# 2016_FDP_PROPULSION.net
KiCad netlist of a schematic drawn in Altium Designer
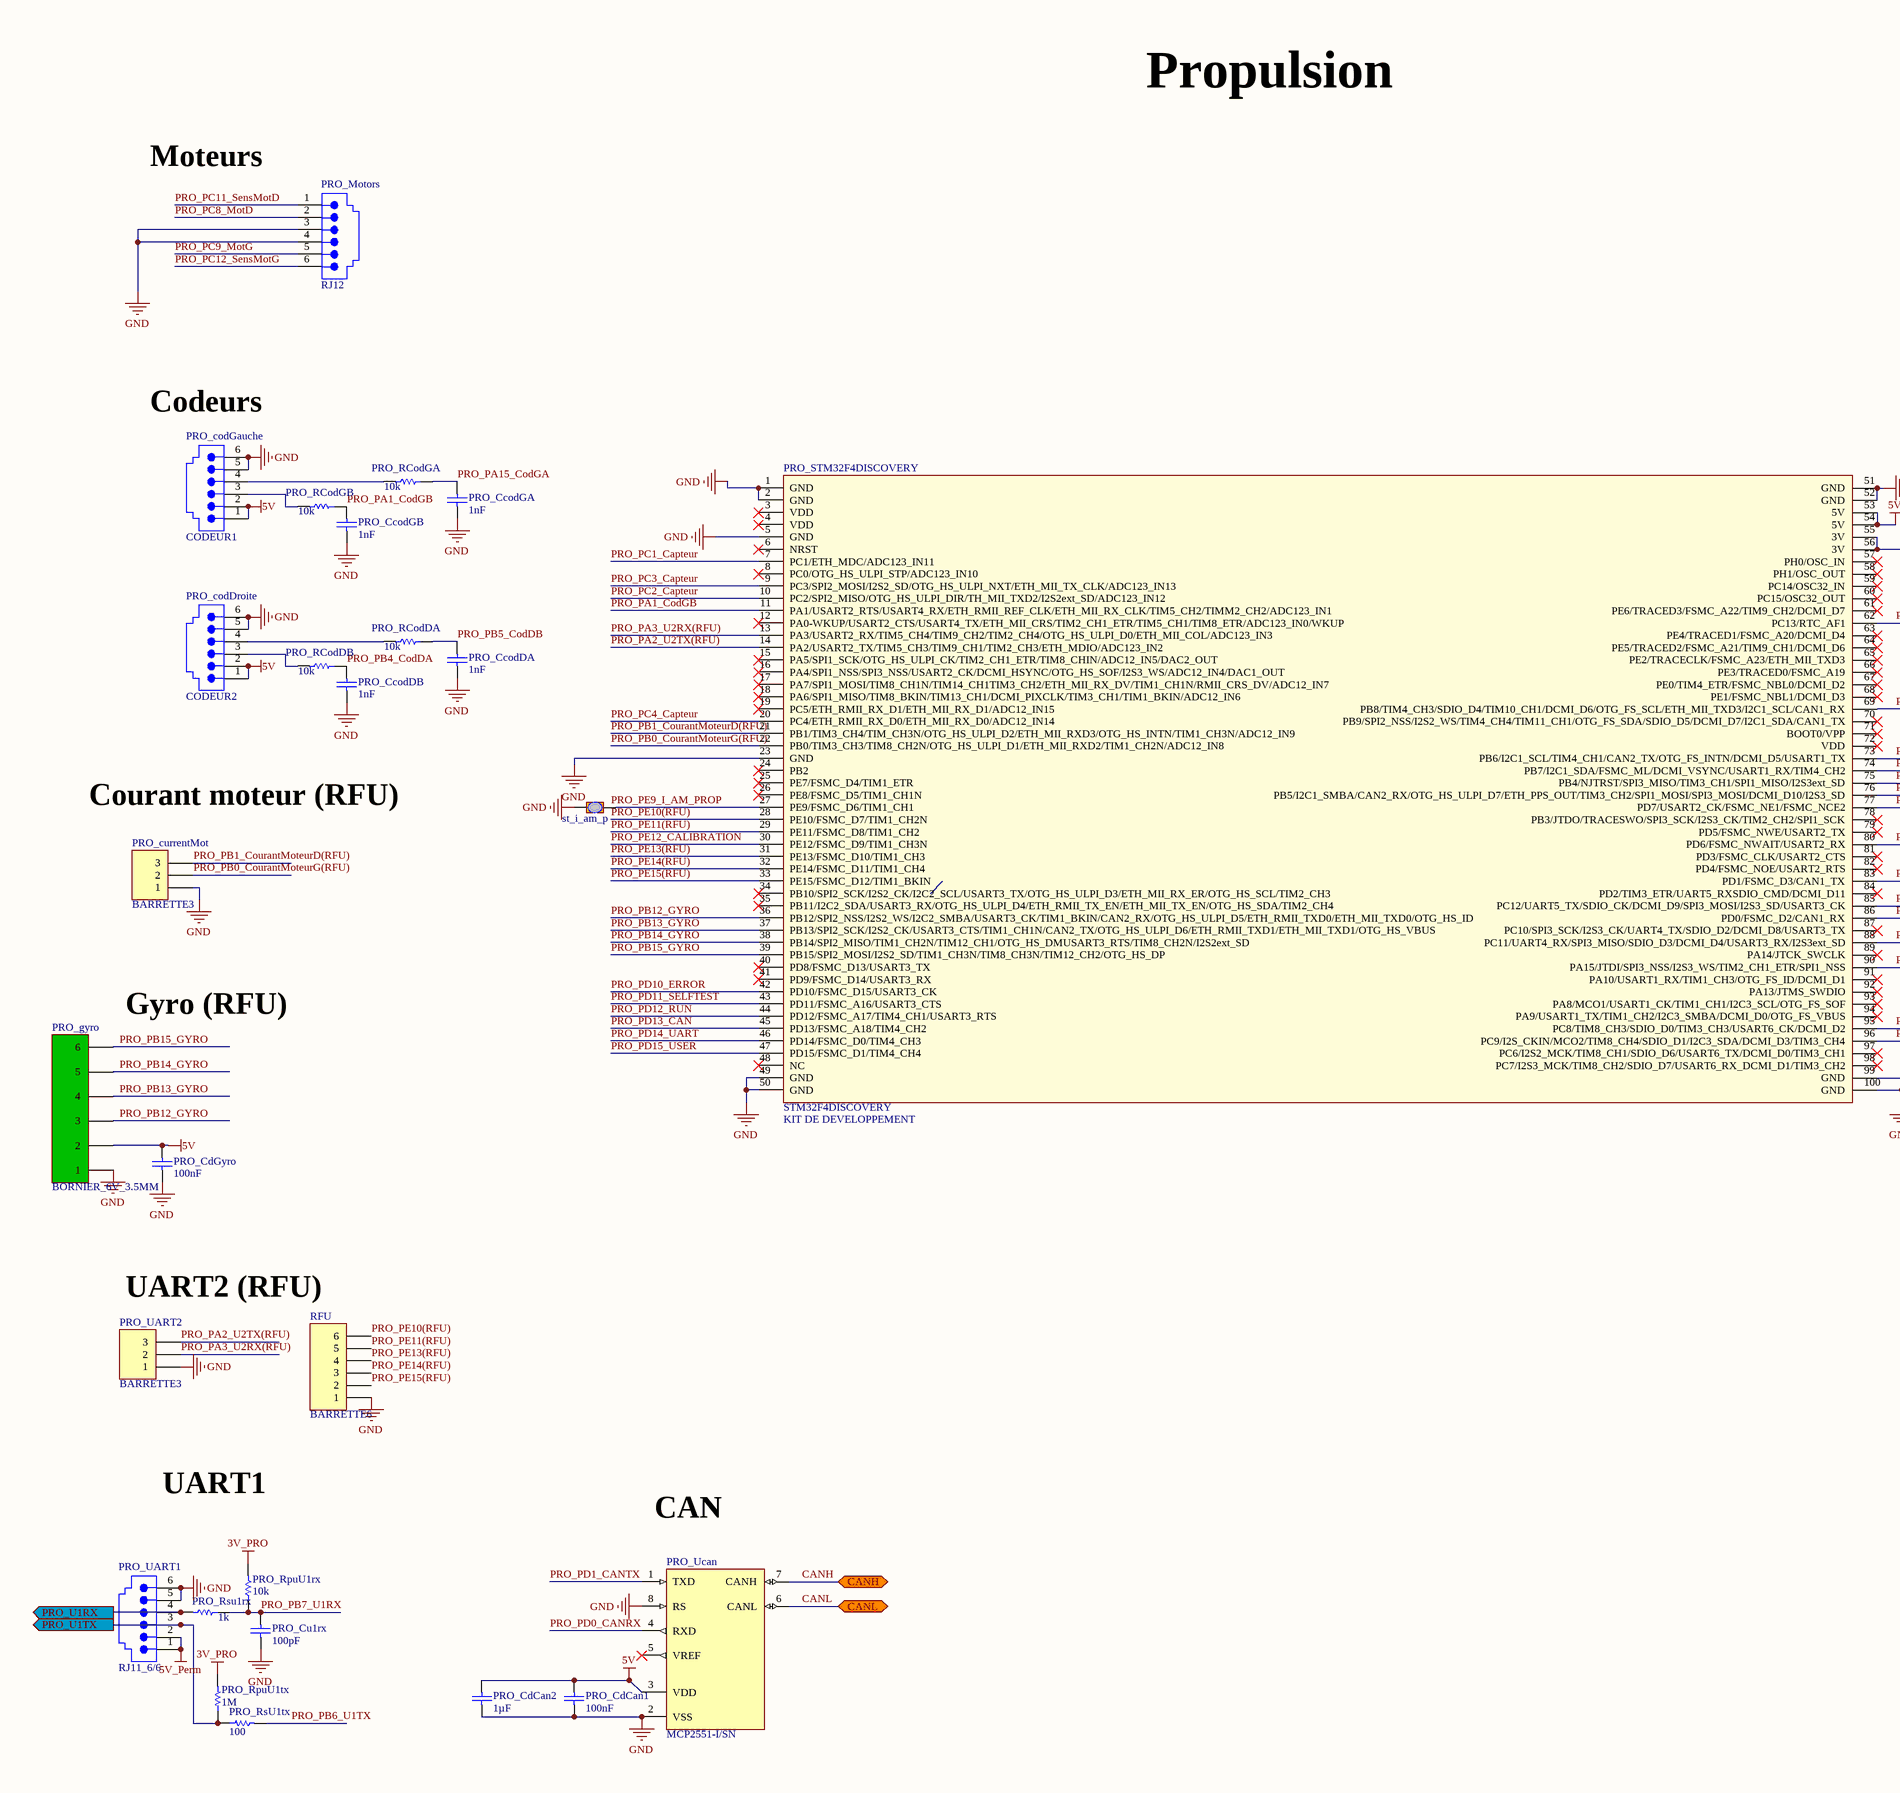
[diagram p0: 2016_FDP_PROPULSION.SchDoc, left]
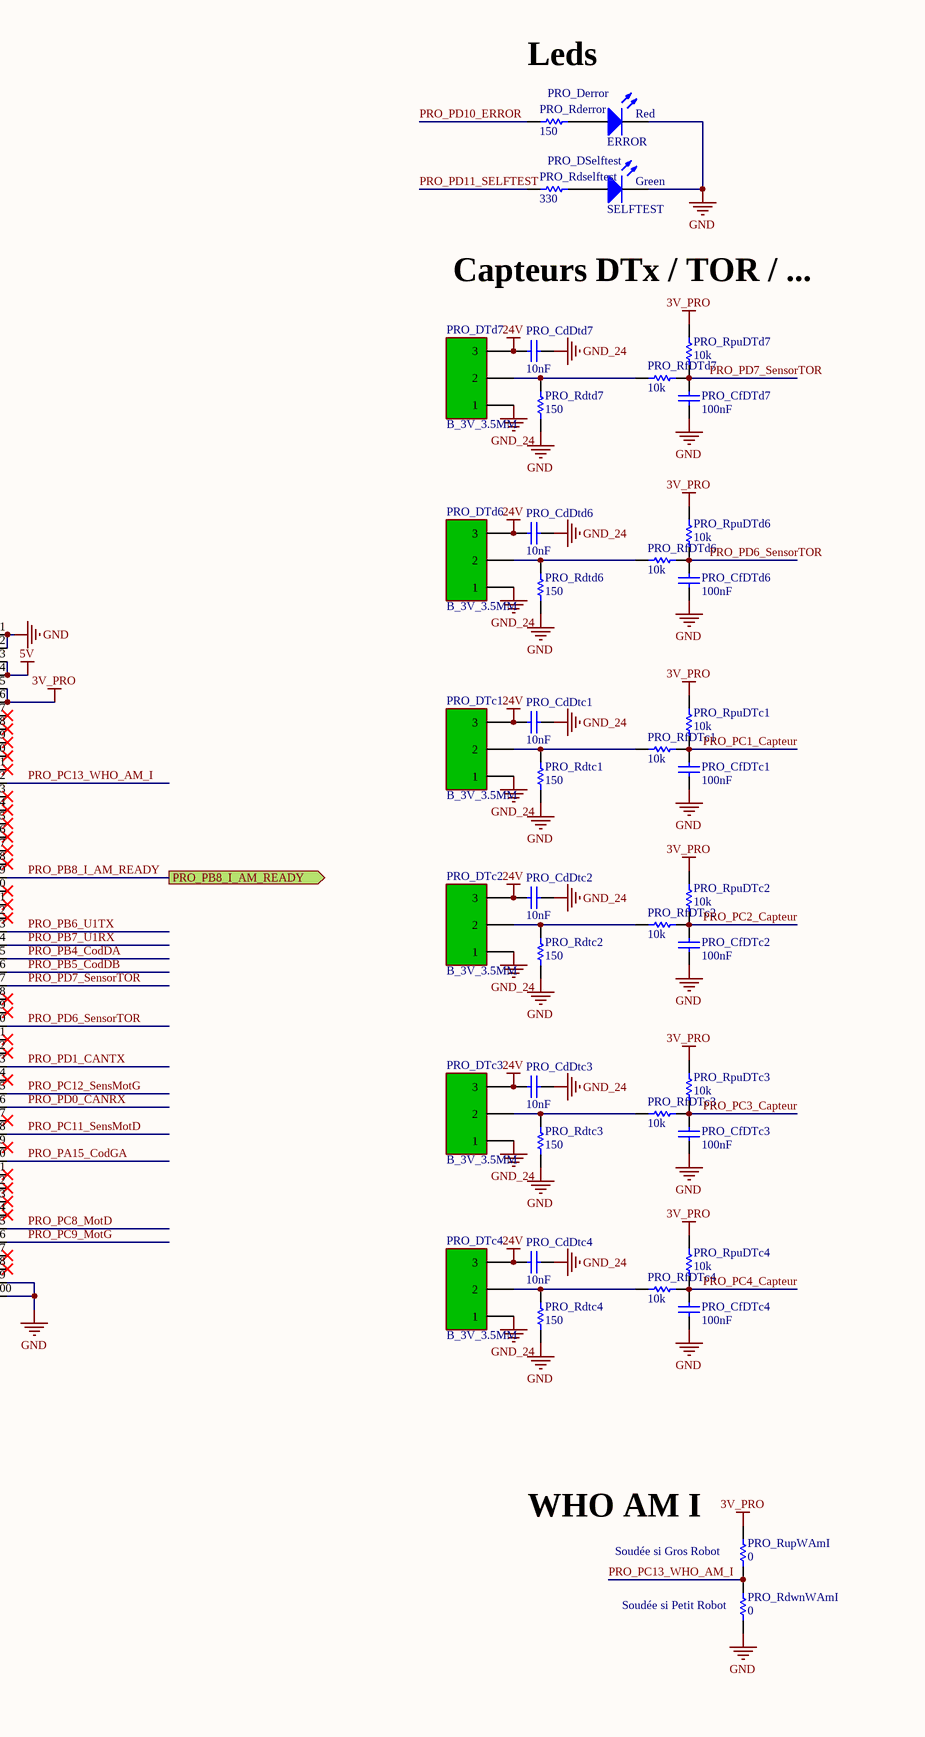
[diagram p1: 2016_FDP_PROPULSION.SchDoc, right]

(export (version "E")
  (design (tool "Eeschema 10.0.6"))
  (components
    (comp (ref "PRO_CcodDA")
      (value "1nF")
      (footprint "C0805_N")
      (description "Capacitor")
      (fields (field (name "PUBLISHER") "Altium Limited"))
      (libsource (lib "_ROBOT") (part "Condensateur"))
    )
    (comp (ref "PRO_CcodDB")
      (value "1nF")
      (footprint "C0805_N")
      (description "Capacitor")
      (fields (field (name "PUBLISHER") "Altium Limited"))
      (libsource (lib "_ROBOT") (part "Condensateur"))
    )
    (comp (ref "PRO_CcodGA")
      (value "1nF")
      (footprint "C0805_N")
      (description "Capacitor")
      (fields (field (name "PUBLISHER") "Altium Limited"))
      (libsource (lib "_ROBOT") (part "Condensateur"))
    )
    (comp (ref "PRO_CcodGB")
      (value "1nF")
      (footprint "C0805_N")
      (description "Capacitor")
      (fields (field (name "PUBLISHER") "Altium Limited"))
      (libsource (lib "_ROBOT") (part "Condensateur"))
    )
    (comp (ref "PRO_CdCan1")
      (value "100nF")
      (footprint "C0805_N")
      (description "Capacitor")
      (fields (field (name "PUBLISHER") "Altium Limited"))
      (libsource (lib "_ROBOT") (part "Condensateur"))
    )
    (comp (ref "PRO_CdCan2")
      (value "1µF")
      (footprint "C0805_N")
      (description "Capacitor")
      (fields (field (name "PUBLISHER") "Altium Limited"))
      (libsource (lib "_ROBOT") (part "Condensateur"))
    )
    (comp (ref "PRO_CdDtc1")
      (value "10nF")
      (footprint "C0805_N")
      (description "Capacitor")
      (fields (field (name "PUBLISHER") "Altium Limited"))
      (libsource (lib "_ROBOT") (part "Condensateur"))
    )
    (comp (ref "PRO_CdDtc2")
      (value "10nF")
      (footprint "C0805_N")
      (description "Capacitor")
      (fields (field (name "PUBLISHER") "Altium Limited"))
      (libsource (lib "_ROBOT") (part "Condensateur"))
    )
    (comp (ref "PRO_CdDtc3")
      (value "10nF")
      (footprint "C0805_N")
      (description "Capacitor")
      (fields (field (name "PUBLISHER") "Altium Limited"))
      (libsource (lib "_ROBOT") (part "Condensateur"))
    )
    (comp (ref "PRO_CdDtc4")
      (value "10nF")
      (footprint "C0805_N")
      (description "Capacitor")
      (fields (field (name "PUBLISHER") "Altium Limited"))
      (libsource (lib "_ROBOT") (part "Condensateur"))
    )
    (comp (ref "PRO_CdDtd6")
      (value "10nF")
      (footprint "C0805_N")
      (description "Capacitor")
      (fields (field (name "PUBLISHER") "Altium Limited"))
      (libsource (lib "_ROBOT") (part "Condensateur"))
    )
    (comp (ref "PRO_CdDtd7")
      (value "10nF")
      (footprint "C0805_N")
      (description "Capacitor")
      (fields (field (name "PUBLISHER") "Altium Limited"))
      (libsource (lib "_ROBOT") (part "Condensateur"))
    )
    (comp (ref "PRO_CdGyro")
      (value "100nF")
      (footprint "C0805_N")
      (description "Capacitor")
      (fields (field (name "PUBLISHER") "Altium Limited"))
      (libsource (lib "_ROBOT") (part "Condensateur"))
    )
    (comp (ref "PRO_CfDTc1")
      (value "100nF")
      (footprint "C0805_N")
      (description "Capacitor")
      (fields (field (name "PUBLISHER") "Altium Limited"))
      (libsource (lib "_ROBOT") (part "Condensateur"))
    )
    (comp (ref "PRO_CfDTc2")
      (value "100nF")
      (footprint "C0805_N")
      (description "Capacitor")
      (fields (field (name "PUBLISHER") "Altium Limited"))
      (libsource (lib "_ROBOT") (part "Condensateur"))
    )
    (comp (ref "PRO_CfDTc3")
      (value "100nF")
      (footprint "C0805_N")
      (description "Capacitor")
      (fields (field (name "PUBLISHER") "Altium Limited"))
      (libsource (lib "_ROBOT") (part "Condensateur"))
    )
    (comp (ref "PRO_CfDTc4")
      (value "100nF")
      (footprint "C0805_N")
      (description "Capacitor")
      (fields (field (name "PUBLISHER") "Altium Limited"))
      (libsource (lib "_ROBOT") (part "Condensateur"))
    )
    (comp (ref "PRO_CfDTd6")
      (value "100nF")
      (footprint "C0805_N")
      (description "Capacitor")
      (fields (field (name "PUBLISHER") "Altium Limited"))
      (libsource (lib "_ROBOT") (part "Condensateur"))
    )
    (comp (ref "PRO_CfDTd7")
      (value "100nF")
      (footprint "C0805_N")
      (description "Capacitor")
      (fields (field (name "PUBLISHER") "Altium Limited"))
      (libsource (lib "_ROBOT") (part "Condensateur"))
    )
    (comp (ref "PRO_codDroite")
      (value "CODEUR2")
      (footprint "RJ11_6/6 - droit")
      (description "Right Angle, Standard Profile, Offset Latch DECconnect, Flangeless PCB Jack")
      (fields (field (name "PUBLISHER") "Altium Limited"))
      (libsource (lib "miniprojet") (part "RJ11_6/6"))
    )
    (comp (ref "PRO_codGauche")
      (value "CODEUR1")
      (footprint "RJ11_6/6 - droit")
      (description "Right Angle, Standard Profile, Offset Latch DECconnect, Flangeless PCB Jack")
      (fields (field (name "PUBLISHER") "Altium Limited"))
      (libsource (lib "miniprojet") (part "RJ11_6/6"))
    )
    (comp (ref "PRO_Cu1rx")
      (value "100pF")
      (footprint "C0805_N")
      (description "Capacitor")
      (fields (field (name "PUBLISHER") "Altium Limited"))
      (libsource (lib "_ROBOT") (part "Condensateur"))
    )
    (comp (ref "PRO_currentMot")
      (value "BARRETTE3")
      (footprint "HE14_3")
      (description "Header, 3-Pin")
      (fields (field (name "PUBLISHER") "Altium Limited"))
      (libsource (lib "Connecteur") (part "BARRETTE3"))
    )
    (comp (ref "PRO_Derror")
      (value "ERROR")
      (footprint "LED_0805")
      (description "Typical LED")
      (fields (field (name "PUBLISHER") "Altium Limited"))
      (libsource (lib "_ROBOT") (part "LED"))
    )
    (comp (ref "PRO_DSelftest")
      (value "SELFTEST")
      (footprint "LED_0805")
      (description "Typical LED")
      (fields (field (name "PUBLISHER") "Altium Limited"))
      (libsource (lib "_ROBOT") (part "LED"))
    )
    (comp (ref "PRO_DTc1")
      (value "B_3V_3.5MM")
      (footprint "BORNIER_3V_3.5MM")
      (libsource (lib "Connecteur") (part "BORNIER_3V_3.5MM"))
    )
    (comp (ref "PRO_DTc2")
      (value "B_3V_3.5MM")
      (footprint "BORNIER_3V_3.5MM")
      (libsource (lib "Connecteur") (part "BORNIER_3V_3.5MM"))
    )
    (comp (ref "PRO_DTc3")
      (value "B_3V_3.5MM")
      (footprint "BORNIER_3V_3.5MM")
      (libsource (lib "Connecteur") (part "BORNIER_3V_3.5MM"))
    )
    (comp (ref "PRO_DTc4")
      (value "B_3V_3.5MM")
      (footprint "BORNIER_3V_3.5MM")
      (libsource (lib "Connecteur") (part "BORNIER_3V_3.5MM"))
    )
    (comp (ref "PRO_DTd6")
      (value "B_3V_3.5MM")
      (footprint "BORNIER_3V_3.5MM")
      (libsource (lib "Connecteur") (part "BORNIER_3V_3.5MM"))
    )
    (comp (ref "PRO_DTd7")
      (value "B_3V_3.5MM")
      (footprint "BORNIER_3V_3.5MM")
      (libsource (lib "Connecteur") (part "BORNIER_3V_3.5MM"))
    )
    (comp (ref "PRO_gyro")
      (value "BORNIER_6V_3.5MM")
      (footprint "BORNIER_6V_3.5MM")
      (libsource (lib "Connecteur") (part "BORNIER_6V_3.5MM"))
    )
    (comp (ref "PRO_Motors")
      (value "RJ12")
      (footprint "RJ11_6/6 - droit")
      (description "Right Angle, Standard Profile, Offset Latch DECconnect, Flangeless PCB Jack")
      (fields (field (name "PUBLISHER") "Altium Limited"))
      (libsource (lib "Connecteur") (part "RJ11_6/6"))
    )
    (comp (ref "PRO_RCodDA")
      (value "10k")
      (footprint "R1206_N")
      (description "Resistor")
      (fields (field (name "PUBLISHER") "Altium Limited"))
      (libsource (lib "_ROBOT") (part "Resistor"))
    )
    (comp (ref "PRO_RCodDB")
      (value "10k")
      (footprint "R1206_N")
      (description "Resistor")
      (fields (field (name "PUBLISHER") "Altium Limited"))
      (libsource (lib "_ROBOT") (part "Resistor"))
    )
    (comp (ref "PRO_RCodGA")
      (value "10k")
      (footprint "R1206_N")
      (description "Resistor")
      (fields (field (name "PUBLISHER") "Altium Limited"))
      (libsource (lib "_ROBOT") (part "Resistor"))
    )
    (comp (ref "PRO_RCodGB")
      (value "10k")
      (footprint "R1206_N")
      (description "Resistor")
      (fields (field (name "PUBLISHER") "Altium Limited"))
      (libsource (lib "_ROBOT") (part "Resistor"))
    )
    (comp (ref "PRO_Rderror")
      (value "150")
      (footprint "R1206_N")
      (description "Resistor")
      (fields (field (name "PUBLISHER") "Altium Limited"))
      (libsource (lib "_ROBOT") (part "Resistor"))
    )
    (comp (ref "PRO_Rdselftest")
      (value "330")
      (footprint "R1206_N")
      (description "Resistor")
      (fields (field (name "PUBLISHER") "Altium Limited"))
      (libsource (lib "_ROBOT") (part "Resistor"))
    )
    (comp (ref "PRO_Rdtc1")
      (value "150")
      (footprint "R1206_N")
      (description "Resistor")
      (fields (field (name "PUBLISHER") "Altium Limited"))
      (libsource (lib "_ROBOT") (part "Resistor"))
    )
    (comp (ref "PRO_Rdtc2")
      (value "150")
      (footprint "R1206_N")
      (description "Resistor")
      (fields (field (name "PUBLISHER") "Altium Limited"))
      (libsource (lib "_ROBOT") (part "Resistor"))
    )
    (comp (ref "PRO_Rdtc3")
      (value "150")
      (footprint "R1206_N")
      (description "Resistor")
      (fields (field (name "PUBLISHER") "Altium Limited"))
      (libsource (lib "_ROBOT") (part "Resistor"))
    )
    (comp (ref "PRO_Rdtc4")
      (value "150")
      (footprint "R1206_N")
      (description "Resistor")
      (fields (field (name "PUBLISHER") "Altium Limited"))
      (libsource (lib "_ROBOT") (part "Resistor"))
    )
    (comp (ref "PRO_Rdtd6")
      (value "150")
      (footprint "R1206_N")
      (description "Resistor")
      (fields (field (name "PUBLISHER") "Altium Limited"))
      (libsource (lib "_ROBOT") (part "Resistor"))
    )
    (comp (ref "PRO_Rdtd7")
      (value "150")
      (footprint "R1206_N")
      (description "Resistor")
      (fields (field (name "PUBLISHER") "Altium Limited"))
      (libsource (lib "_ROBOT") (part "Resistor"))
    )
    (comp (ref "PRO_RdwnWAmI")
      (value "0")
      (footprint "R1206_N")
      (description "Resistor")
      (fields (field (name "PUBLISHER") "Altium Limited"))
      (libsource (lib "_ROBOT") (part "Resistor"))
    )
    (comp (ref "PRO_RfDTc1")
      (value "10k")
      (footprint "R1206_N")
      (description "Resistor")
      (fields (field (name "PUBLISHER") "Altium Limited"))
      (libsource (lib "_ROBOT") (part "Resistor"))
    )
    (comp (ref "PRO_RfDTc2")
      (value "10k")
      (footprint "R1206_N")
      (description "Resistor")
      (fields (field (name "PUBLISHER") "Altium Limited"))
      (libsource (lib "_ROBOT") (part "Resistor"))
    )
    (comp (ref "PRO_RfDTc3")
      (value "10k")
      (footprint "R1206_N")
      (description "Resistor")
      (fields (field (name "PUBLISHER") "Altium Limited"))
      (libsource (lib "_ROBOT") (part "Resistor"))
    )
    (comp (ref "PRO_RfDTc4")
      (value "10k")
      (footprint "R1206_N")
      (description "Resistor")
      (fields (field (name "PUBLISHER") "Altium Limited"))
      (libsource (lib "_ROBOT") (part "Resistor"))
    )
    (comp (ref "PRO_RfDTd6")
      (value "10k")
      (footprint "R1206_N")
      (description "Resistor")
      (fields (field (name "PUBLISHER") "Altium Limited"))
      (libsource (lib "_ROBOT") (part "Resistor"))
    )
    (comp (ref "PRO_RfDTd7")
      (value "10k")
      (footprint "R1206_N")
      (description "Resistor")
      (fields (field (name "PUBLISHER") "Altium Limited"))
      (libsource (lib "_ROBOT") (part "Resistor"))
    )
    (comp (ref "PRO_RpuDTc1")
      (value "10k")
      (footprint "R1206_N")
      (description "Resistor")
      (fields (field (name "PUBLISHER") "Altium Limited"))
      (libsource (lib "_ROBOT") (part "Resistor"))
    )
    (comp (ref "PRO_RpuDTc2")
      (value "10k")
      (footprint "R1206_N")
      (description "Resistor")
      (fields (field (name "PUBLISHER") "Altium Limited"))
      (libsource (lib "_ROBOT") (part "Resistor"))
    )
    (comp (ref "PRO_RpuDTc3")
      (value "10k")
      (footprint "R1206_N")
      (description "Resistor")
      (fields (field (name "PUBLISHER") "Altium Limited"))
      (libsource (lib "_ROBOT") (part "Resistor"))
    )
    (comp (ref "PRO_RpuDTc4")
      (value "10k")
      (footprint "R1206_N")
      (description "Resistor")
      (fields (field (name "PUBLISHER") "Altium Limited"))
      (libsource (lib "_ROBOT") (part "Resistor"))
    )
    (comp (ref "PRO_RpuDTd6")
      (value "10k")
      (footprint "R1206_N")
      (description "Resistor")
      (fields (field (name "PUBLISHER") "Altium Limited"))
      (libsource (lib "_ROBOT") (part "Resistor"))
    )
    (comp (ref "PRO_RpuDTd7")
      (value "10k")
      (footprint "R1206_N")
      (description "Resistor")
      (fields (field (name "PUBLISHER") "Altium Limited"))
      (libsource (lib "_ROBOT") (part "Resistor"))
    )
    (comp (ref "PRO_RpuU1rx")
      (value "10k")
      (footprint "R1206_N")
      (description "Resistor")
      (fields (field (name "PUBLISHER") "Altium Limited"))
      (libsource (lib "_ROBOT") (part "Resistor"))
    )
    (comp (ref "PRO_RpuU1tx")
      (value "1M")
      (footprint "R1206_N")
      (description "Resistor")
      (fields (field (name "PUBLISHER") "Altium Limited"))
      (libsource (lib "_ROBOT") (part "Resistor"))
    )
    (comp (ref "PRO_Rsu1rx")
      (value "1k")
      (footprint "R1206_N")
      (description "Resistor")
      (fields (field (name "PUBLISHER") "Altium Limited"))
      (libsource (lib "_ROBOT") (part "Resistor"))
    )
    (comp (ref "PRO_RsU1tx")
      (value "100")
      (footprint "R1206_N")
      (description "Resistor")
      (fields (field (name "PUBLISHER") "Altium Limited"))
      (libsource (lib "_ROBOT") (part "Resistor"))
    )
    (comp (ref "PRO_RupWAmI")
      (value "0")
      (footprint "R1206_N")
      (description "Resistor")
      (fields (field (name "PUBLISHER") "Altium Limited"))
      (libsource (lib "_ROBOT") (part "Resistor"))
    )
    (comp (ref "PRO_STM32F4DISCOVERY")
      (value "STM32F4DISCOVERY")
      (footprint "STM32_F4DISCOVERY")
      (description "KIT DE DEVELOPPEMENT POUR MICROCONTROLEUR STM32F407VGT6")
      (fields (field (name "TYPE") "KIT DE DEVELOPPEMENT"))
      (libsource (lib "circuits integres") (part "STM32F4DISCOVERY"))
    )
    (comp (ref "PRO_UART1")
      (value "RJ11_6/6")
      (footprint "RJ11_6/6 - droit")
      (description "Right Angle, Standard Profile, Offset Latch DECconnect, Flangeless PCB Jack")
      (fields (field (name "PUBLISHER") "Altium Limited"))
      (libsource (lib "Connecteur") (part "RJ11_6/6"))
    )
    (comp (ref "PRO_UART2")
      (value "BARRETTE3")
      (footprint "HE14_3")
      (description "Header, 3-Pin")
      (fields (field (name "PUBLISHER") "Altium Limited"))
      (libsource (lib "Connecteur") (part "BARRETTE3"))
    )
    (comp (ref "PRO_Ucan")
      (value "MCP2551-I/SN")
      (footprint "SO8_N")
      (description "High-Speed CAN Transceiver, 8-Pin SOIC, Industrial Temperature")
      (fields (field (name "PUBLISHER") "Damien Guitton"))
      (libsource (lib "Circuit intégré") (part "MCP2551-I/SN"))
    )
    (comp (ref "RFU")
      (value "BARRETTE6")
      (footprint "HE14_6")
      (description "Header, 6-Pin")
      (fields (field (name "PUBLISHER") "Altium Limited"))
      (libsource (lib "Connecteur") (part "BARRETTE6"))
    )
    (comp (ref "st_i_am_p")
      (value "Goutte Strap_2")
      (footprint "Goutte Strap_2 Pads_Clearance 0.254mm")
      (fields (field (name "PUBLISHER") "Damien Guitton"))
      (libsource (lib "DG_Connecteur") (part "Goutte Strap_2"))
    )
  )
  (nets
    (net (code "1") (name "/CANH") (class "Default")
      (node (ref "PRO_Ucan") (pin "7") (pinfunction "CANH_7") (pintype "bidirectional"))
    )
    (net (code "2") (name "/CANL") (class "Default")
      (node (ref "PRO_Ucan") (pin "6") (pinfunction "CANL_6") (pintype "bidirectional"))
    )
    (net (code "3") (name "/PRO_PA1_CodGB") (class "Default")
      (node (ref "PRO_CcodGB") (pin "2") (pinfunction "2_2") (pintype "passive"))
      (node (ref "PRO_RCodGB") (pin "1") (pinfunction "1_1") (pintype "passive"))
      (node (ref "PRO_STM32F4DISCOVERY") (pin "11") (pinfunction "PA1/USART2_RTS/USART4_RX/ETH_RMII_REF_CLK/ETH_MII_RX_CLK/TIM5_CH2/TIMM2_CH2/ADC123_IN1_11") (pintype "passive"))
    )
    (net (code "4") (name "/PRO_PA2_U2TX(RFU)") (class "Default")
      (node (ref "PRO_STM32F4DISCOVERY") (pin "14") (pinfunction "PA2/USART2_TX/TIM5_CH3/TIM9_CH1/TIM2_CH3/ETH_MDIO/ADC123_IN2_14") (pintype "passive"))
      (node (ref "PRO_UART2") (pin "3") (pinfunction "3_3") (pintype "passive"))
    )
    (net (code "5") (name "/PRO_PA3_U2RX(RFU)") (class "Default")
      (node (ref "PRO_STM32F4DISCOVERY") (pin "13") (pinfunction "PA3/USART2_RX/TIM5_CH4/TIM9_CH2/TIM2_CH4/OTG_HS_ULPI_D0/ETH_MII_COL/ADC123_IN3_13") (pintype "passive"))
      (node (ref "PRO_UART2") (pin "2") (pinfunction "2_2") (pintype "passive"))
    )
    (net (code "6") (name "/PRO_PA15_CodGA") (class "Default")
      (node (ref "PRO_CcodGA") (pin "2") (pinfunction "2_2") (pintype "passive"))
      (node (ref "PRO_RCodGA") (pin "1") (pinfunction "1_1") (pintype "passive"))
      (node (ref "PRO_STM32F4DISCOVERY") (pin "90") (pinfunction "PA15/JTDI/SPI3_NSS/I2S3_WS/TIM2_CH1_ETR/SPI1_NSS_90") (pintype "passive"))
    )
    (net (code "7") (name "/PRO_PB0_CourantMoteurG(RFU)") (class "Default")
      (node (ref "PRO_STM32F4DISCOVERY") (pin "22") (pinfunction "PB0/TIM3_CH3/TIM8_CH2N/OTG_HS_ULPI_D1/ETH_MII_RXD2/TIM1_CH2N/ADC12_IN8_22") (pintype "passive"))
      (node (ref "PRO_currentMot") (pin "2") (pinfunction "2_2") (pintype "passive"))
    )
    (net (code "8") (name "/PRO_PB1_CourantMoteurD(RFU)") (class "Default")
      (node (ref "PRO_STM32F4DISCOVERY") (pin "21") (pinfunction "PB1/TIM3_CH4/TIM_CH3N/OTG_HS_ULPI_D2/ETH_MII_RXD3/OTG_HS_INTN/TIM1_CH3N/ADC12_IN9_21") (pintype "passive"))
      (node (ref "PRO_currentMot") (pin "3") (pinfunction "3_3") (pintype "passive"))
    )
    (net (code "9") (name "/PRO_PB4_CodDA") (class "Default")
      (node (ref "PRO_CcodDB") (pin "2") (pinfunction "2_2") (pintype "passive"))
      (node (ref "PRO_RCodDB") (pin "1") (pinfunction "1_1") (pintype "passive"))
      (node (ref "PRO_STM32F4DISCOVERY") (pin "75") (pinfunction "PB4/NJTRST/SPI3_MISO/TIM3_CH1/SPI1_MISO/I2S3ext_SD_75") (pintype "passive"))
    )
    (net (code "10") (name "/PRO_PB5_CodDB") (class "Default")
      (node (ref "PRO_CcodDA") (pin "2") (pinfunction "2_2") (pintype "passive"))
      (node (ref "PRO_RCodDA") (pin "1") (pinfunction "1_1") (pintype "passive"))
      (node (ref "PRO_STM32F4DISCOVERY") (pin "76") (pinfunction "PB5/I2C1_SMBA/CAN2_RX/OTG_HS_ULPI_D7/ETH_PPS_OUT/TIM3_CH2/SPI1_MOSI/SPI3_MOSI/DCMI_D10/I2S3_SD_76") (pintype "passive"))
    )
    (net (code "11") (name "/PRO_PB6_U1TX") (class "Default")
      (node (ref "PRO_RsU1tx") (pin "2") (pinfunction "2_2") (pintype "passive"))
      (node (ref "PRO_STM32F4DISCOVERY") (pin "73") (pinfunction "PB6/I2C1_SCL/TIM4_CH1/CAN2_TX/OTG_FS_INTN/DCMI_D5/USART1_TX_73") (pintype "passive"))
    )
    (net (code "12") (name "/PRO_PB7_U1RX") (class "Default")
      (node (ref "PRO_Cu1rx") (pin "2") (pinfunction "2_2") (pintype "passive"))
      (node (ref "PRO_RpuU1rx") (pin "1") (pinfunction "1_1") (pintype "passive"))
      (node (ref "PRO_Rsu1rx") (pin "1") (pinfunction "1_1") (pintype "passive"))
      (node (ref "PRO_STM32F4DISCOVERY") (pin "74") (pinfunction "PB7/I2C1_SDA/FSMC_ML/DCMI_VSYNC/USART1_RX/TIM4_CH2_74") (pintype "passive"))
    )
    (net (code "13") (name "/PRO_PB8_I_AM_READY") (class "Default")
      (node (ref "PRO_STM32F4DISCOVERY") (pin "69") (pinfunction "PB8/TIM4_CH3/SDIO_D4/TIM10_CH1/DCMI_D6/OTG_FS_SCL/ETH_MII_TXD3/I2C1_SCL/CAN1_RX_69") (pintype "passive"))
    )
    (net (code "14") (name "/PRO_PB12_GYRO") (class "Default")
      (node (ref "PRO_STM32F4DISCOVERY") (pin "36") (pinfunction "PB12/SPI2_NSS/I2S2_WS/I2C2_SMBA/USART3_CK/TIM1_BKIN/CAN2_RX/OTG_HS_ULPI_D5/ETH_RMII_TXD0/ETH_MII_TXD0/OTG_HS_ID_36") (pintype "passive"))
      (node (ref "PRO_gyro") (pin "3") (pinfunction "3_3") (pintype "passive"))
    )
    (net (code "15") (name "/PRO_PB13_GYRO") (class "Default")
      (node (ref "PRO_STM32F4DISCOVERY") (pin "37") (pinfunction "PB13/SPI2_SCK/I2S2_CK/USART3_CTS/TIM1_CH1N/CAN2_TX/OTG_HS_ULPI_D6/ETH_RMII_TXD1/ETH_MII_TXD1/OTG_HS_VBUS_37") (pintype "passive"))
      (node (ref "PRO_gyro") (pin "4") (pinfunction "4_4") (pintype "passive"))
    )
    (net (code "16") (name "/PRO_PB14_GYRO") (class "Default")
      (node (ref "PRO_STM32F4DISCOVERY") (pin "38") (pinfunction "PB14/SPI2_MISO/TIM1_CH2N/TIM12_CH1/OTG_HS_DMUSART3_RTS/TIM8_CH2N/I2S2ext_SD_38") (pintype "passive"))
      (node (ref "PRO_gyro") (pin "5") (pinfunction "5_5") (pintype "passive"))
    )
    (net (code "17") (name "/PRO_PB15_GYRO") (class "Default")
      (node (ref "PRO_STM32F4DISCOVERY") (pin "39") (pinfunction "PB15/SPI2_MOSI/I2S2_SD/TIM1_CH3N/TIM8_CH3N/TIM12_CH2/OTG_HS_DP_39") (pintype "passive"))
      (node (ref "PRO_gyro") (pin "6") (pinfunction "6_6") (pintype "passive"))
    )
    (net (code "18") (name "/PRO_PC1_Capteur") (class "Default")
      (node (ref "PRO_CfDTc1") (pin "2") (pinfunction "2_2") (pintype "passive"))
      (node (ref "PRO_RfDTc1") (pin "2") (pinfunction "2_2") (pintype "passive"))
      (node (ref "PRO_RpuDTc1") (pin "1") (pinfunction "1_1") (pintype "passive"))
      (node (ref "PRO_STM32F4DISCOVERY") (pin "7") (pinfunction "PC1/ETH_MDC/ADC123_IN11_7") (pintype "passive"))
    )
    (net (code "19") (name "/PRO_PC2_Capteur") (class "Default")
      (node (ref "PRO_CfDTc2") (pin "2") (pinfunction "2_2") (pintype "passive"))
      (node (ref "PRO_RfDTc2") (pin "2") (pinfunction "2_2") (pintype "passive"))
      (node (ref "PRO_RpuDTc2") (pin "1") (pinfunction "1_1") (pintype "passive"))
      (node (ref "PRO_STM32F4DISCOVERY") (pin "10") (pinfunction "PC2/SPI2_MISO/OTG_HS_ULPI_DIR/TH_MII_TXD2/I2S2ext_SD/ADC123_IN12_10") (pintype "passive"))
    )
    (net (code "20") (name "/PRO_PC3_Capteur") (class "Default")
      (node (ref "PRO_CfDTc3") (pin "2") (pinfunction "2_2") (pintype "passive"))
      (node (ref "PRO_RfDTc3") (pin "2") (pinfunction "2_2") (pintype "passive"))
      (node (ref "PRO_RpuDTc3") (pin "1") (pinfunction "1_1") (pintype "passive"))
      (node (ref "PRO_STM32F4DISCOVERY") (pin "9") (pinfunction "PC3/SPI2_MOSI/I2S2_SD/OTG_HS_ULPI_NXT/ETH_MII_TX_CLK/ADC123_IN13_9") (pintype "passive"))
    )
    (net (code "21") (name "/PRO_PC4_Capteur") (class "Default")
      (node (ref "PRO_CfDTc4") (pin "2") (pinfunction "2_2") (pintype "passive"))
      (node (ref "PRO_RfDTc4") (pin "2") (pinfunction "2_2") (pintype "passive"))
      (node (ref "PRO_RpuDTc4") (pin "1") (pinfunction "1_1") (pintype "passive"))
      (node (ref "PRO_STM32F4DISCOVERY") (pin "20") (pinfunction "PC4/ETH_RMII_RX_D0/ETH_MII_RX_D0/ADC12_IN14_20") (pintype "passive"))
    )
    (net (code "22") (name "/PRO_PC8_MotD") (class "Default")
      (node (ref "PRO_Motors") (pin "2") (pinfunction "2_2") (pintype "passive"))
      (node (ref "PRO_STM32F4DISCOVERY") (pin "95") (pinfunction "PC8/TIM8_CH3/SDIO_D0/TIM3_CH3/USART6_CK/DCMI_D2_95") (pintype "passive"))
    )
    (net (code "23") (name "/PRO_PC9_MotG") (class "Default")
      (node (ref "PRO_Motors") (pin "5") (pinfunction "5_5") (pintype "passive"))
      (node (ref "PRO_STM32F4DISCOVERY") (pin "96") (pinfunction "PC9/I2S_CKIN/MCO2/TIM8_CH4/SDIO_D1/I2C3_SDA/DCMI_D3/TIM3_CH4_96") (pintype "passive"))
    )
    (net (code "24") (name "/PRO_PC11_SensMotD") (class "Default")
      (node (ref "PRO_Motors") (pin "1") (pinfunction "1_1") (pintype "passive"))
      (node (ref "PRO_STM32F4DISCOVERY") (pin "88") (pinfunction "PC11/UART4_RX/SPI3_MISO/SDIO_D3/DCMI_D4/USART3_RX/I2S3ext_SD_88") (pintype "passive"))
    )
    (net (code "25") (name "/PRO_PC12_SensMotG") (class "Default")
      (node (ref "PRO_Motors") (pin "6") (pinfunction "6_6") (pintype "passive"))
      (node (ref "PRO_STM32F4DISCOVERY") (pin "85") (pinfunction "PC12/UART5_TX/SDIO_CK/DCMI_D9/SPI3_MOSI/I2S3_SD/USART3_CK_85") (pintype "passive"))
    )
    (net (code "26") (name "/PRO_PC13_WHO_AM_I") (class "Default")
      (node (ref "PRO_RdwnWAmI") (pin "2") (pinfunction "2_2") (pintype "passive"))
      (node (ref "PRO_RupWAmI") (pin "1") (pinfunction "1_1") (pintype "passive"))
      (node (ref "PRO_STM32F4DISCOVERY") (pin "62") (pinfunction "PC13/RTC_AF1_62") (pintype "passive"))
    )
    (net (code "27") (name "/PRO_PD0_CANRX") (class "Default")
      (node (ref "PRO_STM32F4DISCOVERY") (pin "86") (pinfunction "PD0/FSMC_D2/CAN1_RX_86") (pintype "passive"))
      (node (ref "PRO_Ucan") (pin "4") (pinfunction "RXD_4") (pintype "output"))
    )
    (net (code "28") (name "/PRO_PD1_CANTX") (class "Default")
      (node (ref "PRO_STM32F4DISCOVERY") (pin "83") (pinfunction "PD1/FSMC_D3/CAN1_TX_83") (pintype "passive"))
      (node (ref "PRO_Ucan") (pin "1") (pinfunction "TXD_1") (pintype "input"))
    )
    (net (code "29") (name "/PRO_PD6_SensorTOR") (class "Default")
      (node (ref "PRO_CfDTd6") (pin "2") (pinfunction "2_2") (pintype "passive"))
      (node (ref "PRO_RfDTd6") (pin "2") (pinfunction "2_2") (pintype "passive"))
      (node (ref "PRO_RpuDTd6") (pin "1") (pinfunction "1_1") (pintype "passive"))
      (node (ref "PRO_STM32F4DISCOVERY") (pin "80") (pinfunction "PD6/FSMC_NWAIT/USART2_RX_80") (pintype "passive"))
    )
    (net (code "30") (name "/PRO_PD7_SensorTOR") (class "Default")
      (node (ref "PRO_CfDTd7") (pin "2") (pinfunction "2_2") (pintype "passive"))
      (node (ref "PRO_RfDTd7") (pin "2") (pinfunction "2_2") (pintype "passive"))
      (node (ref "PRO_RpuDTd7") (pin "1") (pinfunction "1_1") (pintype "passive"))
      (node (ref "PRO_STM32F4DISCOVERY") (pin "77") (pinfunction "PD7/USART2_CK/FSMC_NE1/FSMC_NCE2_77") (pintype "passive"))
    )
    (net (code "31") (name "/PRO_PD10_ERROR") (class "Default")
      (node (ref "PRO_Rderror") (pin "1") (pinfunction "1_1") (pintype "passive"))
      (node (ref "PRO_STM32F4DISCOVERY") (pin "42") (pinfunction "PD10/FSMC_D15/USART3_CK_42") (pintype "passive"))
    )
    (net (code "32") (name "/PRO_PD11_SELFTEST") (class "Default")
      (node (ref "PRO_Rdselftest") (pin "1") (pinfunction "1_1") (pintype "passive"))
      (node (ref "PRO_STM32F4DISCOVERY") (pin "43") (pinfunction "PD11/FSMC_A16/USART3_CTS_43") (pintype "passive"))
    )
    (net (code "33") (name "/PRO_PD12_RUN") (class "Default")
      (node (ref "PRO_STM32F4DISCOVERY") (pin "44") (pinfunction "PD12/FSMC_A17/TIM4_CH1/USART3_RTS_44") (pintype "passive"))
    )
    (net (code "34") (name "/PRO_PD13_CAN") (class "Default")
      (node (ref "PRO_STM32F4DISCOVERY") (pin "45") (pinfunction "PD13/FSMC_A18/TIM4_CH2_45") (pintype "passive"))
    )
    (net (code "35") (name "/PRO_PD14_UART") (class "Default")
      (node (ref "PRO_STM32F4DISCOVERY") (pin "46") (pinfunction "PD14/FSMC_D0/TIM4_CH3_46") (pintype "passive"))
    )
    (net (code "36") (name "/PRO_PD15_USER") (class "Default")
      (node (ref "PRO_STM32F4DISCOVERY") (pin "47") (pinfunction "PD15/FSMC_D1/TIM4_CH4_47") (pintype "passive"))
    )
    (net (code "38") (name "/PRO_PE10(RFU)") (class "Default")
      (node (ref "PRO_STM32F4DISCOVERY") (pin "28") (pinfunction "PE10/FSMC_D7/TIM1_CH2N_28") (pintype "passive"))
      (node (ref "RFU") (pin "6") (pinfunction "6_6") (pintype "passive"))
    )
    (net (code "39") (name "/PRO_PE11(RFU)") (class "Default")
      (node (ref "PRO_STM32F4DISCOVERY") (pin "29") (pinfunction "PE11/FSMC_D8/TIM1_CH2_29") (pintype "passive"))
      (node (ref "RFU") (pin "5") (pinfunction "5_5") (pintype "passive"))
    )
    (net (code "40") (name "/PRO_PE12_CALIBRATION") (class "Default")
      (node (ref "PRO_STM32F4DISCOVERY") (pin "30") (pinfunction "PE12/FSMC_D9/TIM1_CH3N_30") (pintype "passive"))
    )
    (net (code "41") (name "/PRO_PE13(RFU)") (class "Default")
      (node (ref "PRO_STM32F4DISCOVERY") (pin "31") (pinfunction "PE13/FSMC_D10/TIM1_CH3_31") (pintype "passive"))
      (node (ref "RFU") (pin "4") (pinfunction "4_4") (pintype "passive"))
    )
    (net (code "42") (name "/PRO_PE14(RFU)") (class "Default")
      (node (ref "PRO_STM32F4DISCOVERY") (pin "32") (pinfunction "PE14/FSMC_D11/TIM1_CH4_32") (pintype "passive"))
      (node (ref "RFU") (pin "3") (pinfunction "3_3") (pintype "passive"))
    )
    (net (code "43") (name "/PRO_PE15(RFU)") (class "Default")
      (node (ref "PRO_STM32F4DISCOVERY") (pin "33") (pinfunction "PE15/FSMC_D12/TIM1_BKIN_33") (pintype "passive"))
      (node (ref "RFU") (pin "2") (pinfunction "2_2") (pintype "passive"))
    )
    (net (code "44") (name "/PRO_U1RX") (class "Default")
      (node (ref "PRO_Rsu1rx") (pin "2") (pinfunction "2_2") (pintype "passive"))
      (node (ref "PRO_UART1") (pin "4") (pinfunction "4_4") (pintype "passive"))
    )
    (net (code "45") (name "/PRO_U1TX") (class "Default")
      (node (ref "PRO_RpuU1tx") (pin "1") (pinfunction "1_1") (pintype "passive"))
      (node (ref "PRO_RsU1tx") (pin "1") (pinfunction "1_1") (pintype "passive"))
      (node (ref "PRO_UART1") (pin "3") (pinfunction "3_3") (pintype "passive"))
    )
    (net (code "46") (name "3V_PRO") (class "Default")
      (node (ref "PRO_RpuDTc1") (pin "2") (pinfunction "2_2") (pintype "passive"))
      (node (ref "PRO_RpuDTc2") (pin "2") (pinfunction "2_2") (pintype "passive"))
      (node (ref "PRO_RpuDTc3") (pin "2") (pinfunction "2_2") (pintype "passive"))
      (node (ref "PRO_RpuDTc4") (pin "2") (pinfunction "2_2") (pintype "passive"))
      (node (ref "PRO_RpuDTd6") (pin "2") (pinfunction "2_2") (pintype "passive"))
      (node (ref "PRO_RpuDTd7") (pin "2") (pinfunction "2_2") (pintype "passive"))
      (node (ref "PRO_RpuU1rx") (pin "2") (pinfunction "2_2") (pintype "passive"))
      (node (ref "PRO_RpuU1tx") (pin "2") (pinfunction "2_2") (pintype "passive"))
      (node (ref "PRO_RupWAmI") (pin "2") (pinfunction "2_2") (pintype "passive"))
      (node (ref "PRO_STM32F4DISCOVERY") (pin "55") (pinfunction "3V_55") (pintype "passive"))
      (node (ref "PRO_STM32F4DISCOVERY") (pin "56") (pinfunction "3V_56") (pintype "passive"))
    )
    (net (code "47") (name "5V") (class "Default")
      (node (ref "PRO_CdCan1") (pin "2") (pinfunction "2_2") (pintype "passive"))
      (node (ref "PRO_CdCan2") (pin "2") (pinfunction "2_2") (pintype "passive"))
      (node (ref "PRO_CdGyro") (pin "2") (pinfunction "2_2") (pintype "passive"))
      (node (ref "PRO_STM32F4DISCOVERY") (pin "53") (pinfunction "5V_53") (pintype "passive"))
      (node (ref "PRO_STM32F4DISCOVERY") (pin "54") (pinfunction "5V_54") (pintype "passive"))
      (node (ref "PRO_Ucan") (pin "3") (pinfunction "VDD_3") (pintype "power_in"))
      (node (ref "PRO_codDroite") (pin "1") (pinfunction "1_1") (pintype "passive"))
      (node (ref "PRO_codDroite") (pin "2") (pinfunction "2_2") (pintype "passive"))
      (node (ref "PRO_codGauche") (pin "1") (pinfunction "1_1") (pintype "passive"))
      (node (ref "PRO_codGauche") (pin "2") (pinfunction "2_2") (pintype "passive"))
      (node (ref "PRO_gyro") (pin "2") (pinfunction "2_2") (pintype "passive"))
    )
    (net (code "48") (name "5V_Perm") (class "Default")
      (node (ref "PRO_UART1") (pin "1") (pinfunction "1_1") (pintype "passive"))
      (node (ref "PRO_UART1") (pin "2") (pinfunction "2_2") (pintype "passive"))
    )
    (net (code "49") (name "24V") (class "Default")
      (node (ref "PRO_CdDtc1") (pin "2") (pinfunction "2_2") (pintype "passive"))
      (node (ref "PRO_CdDtc2") (pin "2") (pinfunction "2_2") (pintype "passive"))
      (node (ref "PRO_CdDtc3") (pin "2") (pinfunction "2_2") (pintype "passive"))
      (node (ref "PRO_CdDtc4") (pin "2") (pinfunction "2_2") (pintype "passive"))
      (node (ref "PRO_CdDtd6") (pin "2") (pinfunction "2_2") (pintype "passive"))
      (node (ref "PRO_CdDtd7") (pin "2") (pinfunction "2_2") (pintype "passive"))
      (node (ref "PRO_DTc1") (pin "3") (pinfunction "3_3") (pintype "passive"))
      (node (ref "PRO_DTc2") (pin "3") (pinfunction "3_3") (pintype "passive"))
      (node (ref "PRO_DTc3") (pin "3") (pinfunction "3_3") (pintype "passive"))
      (node (ref "PRO_DTc4") (pin "3") (pinfunction "3_3") (pintype "passive"))
      (node (ref "PRO_DTd6") (pin "3") (pinfunction "3_3") (pintype "passive"))
      (node (ref "PRO_DTd7") (pin "3") (pinfunction "3_3") (pintype "passive"))
    )
    (net (code "50") (name "GND") (class "Default")
      (node (ref "PRO_CcodDA") (pin "1") (pinfunction "1_1") (pintype "passive"))
      (node (ref "PRO_CcodDB") (pin "1") (pinfunction "1_1") (pintype "passive"))
      (node (ref "PRO_CcodGA") (pin "1") (pinfunction "1_1") (pintype "passive"))
      (node (ref "PRO_CcodGB") (pin "1") (pinfunction "1_1") (pintype "passive"))
      (node (ref "PRO_CdCan1") (pin "1") (pinfunction "1_1") (pintype "passive"))
      (node (ref "PRO_CdCan2") (pin "1") (pinfunction "1_1") (pintype "passive"))
      (node (ref "PRO_CdGyro") (pin "1") (pinfunction "1_1") (pintype "passive"))
      (node (ref "PRO_CfDTc1") (pin "1") (pinfunction "1_1") (pintype "passive"))
      (node (ref "PRO_CfDTc2") (pin "1") (pinfunction "1_1") (pintype "passive"))
      (node (ref "PRO_CfDTc3") (pin "1") (pinfunction "1_1") (pintype "passive"))
      (node (ref "PRO_CfDTc4") (pin "1") (pinfunction "1_1") (pintype "passive"))
      (node (ref "PRO_CfDTd6") (pin "1") (pinfunction "1_1") (pintype "passive"))
      (node (ref "PRO_CfDTd7") (pin "1") (pinfunction "1_1") (pintype "passive"))
      (node (ref "PRO_Cu1rx") (pin "1") (pinfunction "1_1") (pintype "passive"))
      (node (ref "PRO_DSelftest") (pin "2") (pinfunction "K_2") (pintype "passive"))
      (node (ref "PRO_Derror") (pin "2") (pinfunction "K_2") (pintype "passive"))
      (node (ref "PRO_Motors") (pin "3") (pinfunction "3_3") (pintype "passive"))
      (node (ref "PRO_Motors") (pin "4") (pinfunction "4_4") (pintype "passive"))
      (node (ref "PRO_Rdtc1") (pin "1") (pinfunction "1_1") (pintype "passive"))
      (node (ref "PRO_Rdtc2") (pin "1") (pinfunction "1_1") (pintype "passive"))
      (node (ref "PRO_Rdtc3") (pin "1") (pinfunction "1_1") (pintype "passive"))
      (node (ref "PRO_Rdtc4") (pin "1") (pinfunction "1_1") (pintype "passive"))
      (node (ref "PRO_Rdtd6") (pin "1") (pinfunction "1_1") (pintype "passive"))
      (node (ref "PRO_Rdtd7") (pin "1") (pinfunction "1_1") (pintype "passive"))
      (node (ref "PRO_RdwnWAmI") (pin "1") (pinfunction "1_1") (pintype "passive"))
      (node (ref "PRO_STM32F4DISCOVERY") (pin "1") (pinfunction "GND_1") (pintype "passive"))
      (node (ref "PRO_STM32F4DISCOVERY") (pin "100") (pinfunction "GND_100") (pintype "passive"))
      (node (ref "PRO_STM32F4DISCOVERY") (pin "2") (pinfunction "GND_2") (pintype "passive"))
      (node (ref "PRO_STM32F4DISCOVERY") (pin "23") (pinfunction "GND_23") (pintype "passive"))
      (node (ref "PRO_STM32F4DISCOVERY") (pin "49") (pinfunction "GND_49") (pintype "passive"))
      (node (ref "PRO_STM32F4DISCOVERY") (pin "5") (pinfunction "GND_5") (pintype "passive"))
      (node (ref "PRO_STM32F4DISCOVERY") (pin "50") (pinfunction "GND_50") (pintype "passive"))
      (node (ref "PRO_STM32F4DISCOVERY") (pin "51") (pinfunction "GND_51") (pintype "passive"))
      (node (ref "PRO_STM32F4DISCOVERY") (pin "52") (pinfunction "GND_52") (pintype "passive"))
      (node (ref "PRO_STM32F4DISCOVERY") (pin "99") (pinfunction "GND_99") (pintype "passive"))
      (node (ref "PRO_UART1") (pin "5") (pinfunction "5_5") (pintype "passive"))
      (node (ref "PRO_UART1") (pin "6") (pinfunction "6_6") (pintype "passive"))
      (node (ref "PRO_UART2") (pin "1") (pinfunction "1_1") (pintype "passive"))
      (node (ref "PRO_Ucan") (pin "2") (pinfunction "VSS_2") (pintype "power_in"))
      (node (ref "PRO_Ucan") (pin "8") (pinfunction "RS_8") (pintype "input"))
      (node (ref "PRO_codDroite") (pin "5") (pinfunction "5_5") (pintype "passive"))
      (node (ref "PRO_codDroite") (pin "6") (pinfunction "6_6") (pintype "passive"))
      (node (ref "PRO_codGauche") (pin "5") (pinfunction "5_5") (pintype "passive"))
      (node (ref "PRO_codGauche") (pin "6") (pinfunction "6_6") (pintype "passive"))
      (node (ref "PRO_currentMot") (pin "1") (pinfunction "1_1") (pintype "passive"))
      (node (ref "PRO_gyro") (pin "1") (pinfunction "1_1") (pintype "passive"))
      (node (ref "RFU") (pin "1") (pinfunction "1_1") (pintype "passive"))
      (node (ref "st_i_am_p") (pin "1") (pinfunction "1_1") (pintype "passive"))
    )
    (net (code "51") (name "GND_24") (class "Default")
      (node (ref "PRO_CdDtc1") (pin "1") (pinfunction "1_1") (pintype "passive"))
      (node (ref "PRO_CdDtc2") (pin "1") (pinfunction "1_1") (pintype "passive"))
      (node (ref "PRO_CdDtc3") (pin "1") (pinfunction "1_1") (pintype "passive"))
      (node (ref "PRO_CdDtc4") (pin "1") (pinfunction "1_1") (pintype "passive"))
      (node (ref "PRO_CdDtd6") (pin "1") (pinfunction "1_1") (pintype "passive"))
      (node (ref "PRO_CdDtd7") (pin "1") (pinfunction "1_1") (pintype "passive"))
      (node (ref "PRO_DTc1") (pin "1") (pinfunction "1_1") (pintype "passive"))
      (node (ref "PRO_DTc2") (pin "1") (pinfunction "1_1") (pintype "passive"))
      (node (ref "PRO_DTc3") (pin "1") (pinfunction "1_1") (pintype "passive"))
      (node (ref "PRO_DTc4") (pin "1") (pinfunction "1_1") (pintype "passive"))
      (node (ref "PRO_DTd6") (pin "1") (pinfunction "1_1") (pintype "passive"))
      (node (ref "PRO_DTd7") (pin "1") (pinfunction "1_1") (pintype "passive"))
    )
    (net (code "52") (name "Net-(PRO_DSelftest-A)") (class "Default")
      (node (ref "PRO_DSelftest") (pin "1") (pinfunction "A_1") (pintype "passive"))
      (node (ref "PRO_Rdselftest") (pin "2") (pinfunction "2_2") (pintype "passive"))
    )
    (net (code "53") (name "Net-(PRO_DTc1-Pad2)") (class "Default")
      (node (ref "PRO_DTc1") (pin "2") (pinfunction "2_2") (pintype "passive"))
      (node (ref "PRO_Rdtc1") (pin "2") (pinfunction "2_2") (pintype "passive"))
      (node (ref "PRO_RfDTc1") (pin "1") (pinfunction "1_1") (pintype "passive"))
    )
    (net (code "54") (name "Net-(PRO_DTc2-Pad2)") (class "Default")
      (node (ref "PRO_DTc2") (pin "2") (pinfunction "2_2") (pintype "passive"))
      (node (ref "PRO_Rdtc2") (pin "2") (pinfunction "2_2") (pintype "passive"))
      (node (ref "PRO_RfDTc2") (pin "1") (pinfunction "1_1") (pintype "passive"))
    )
    (net (code "55") (name "Net-(PRO_DTc3-Pad2)") (class "Default")
      (node (ref "PRO_DTc3") (pin "2") (pinfunction "2_2") (pintype "passive"))
      (node (ref "PRO_Rdtc3") (pin "2") (pinfunction "2_2") (pintype "passive"))
      (node (ref "PRO_RfDTc3") (pin "1") (pinfunction "1_1") (pintype "passive"))
    )
    (net (code "56") (name "Net-(PRO_DTc4-Pad2)") (class "Default")
      (node (ref "PRO_DTc4") (pin "2") (pinfunction "2_2") (pintype "passive"))
      (node (ref "PRO_Rdtc4") (pin "2") (pinfunction "2_2") (pintype "passive"))
      (node (ref "PRO_RfDTc4") (pin "1") (pinfunction "1_1") (pintype "passive"))
    )
    (net (code "57") (name "Net-(PRO_DTd6-Pad2)") (class "Default")
      (node (ref "PRO_DTd6") (pin "2") (pinfunction "2_2") (pintype "passive"))
      (node (ref "PRO_Rdtd6") (pin "2") (pinfunction "2_2") (pintype "passive"))
      (node (ref "PRO_RfDTd6") (pin "1") (pinfunction "1_1") (pintype "passive"))
    )
    (net (code "58") (name "Net-(PRO_DTd7-Pad2)") (class "Default")
      (node (ref "PRO_DTd7") (pin "2") (pinfunction "2_2") (pintype "passive"))
      (node (ref "PRO_Rdtd7") (pin "2") (pinfunction "2_2") (pintype "passive"))
      (node (ref "PRO_RfDTd7") (pin "1") (pinfunction "1_1") (pintype "passive"))
    )
    (net (code "59") (name "Net-(PRO_Derror-A)") (class "Default")
      (node (ref "PRO_Derror") (pin "1") (pinfunction "A_1") (pintype "passive"))
      (node (ref "PRO_Rderror") (pin "2") (pinfunction "2_2") (pintype "passive"))
    )
    (net (code "60") (name "Net-(PRO_RCodDA-Pad2)") (class "Default")
      (node (ref "PRO_RCodDA") (pin "2") (pinfunction "2_2") (pintype "passive"))
      (node (ref "PRO_codDroite") (pin "4") (pinfunction "4_4") (pintype "passive"))
    )
    (net (code "61") (name "Net-(PRO_RCodDB-Pad2)") (class "Default")
      (node (ref "PRO_RCodDB") (pin "2") (pinfunction "2_2") (pintype "passive"))
      (node (ref "PRO_codDroite") (pin "3") (pinfunction "3_3") (pintype "passive"))
    )
    (net (code "62") (name "Net-(PRO_RCodGA-Pad2)") (class "Default")
      (node (ref "PRO_RCodGA") (pin "2") (pinfunction "2_2") (pintype "passive"))
      (node (ref "PRO_codGauche") (pin "4") (pinfunction "4_4") (pintype "passive"))
    )
    (net (code "63") (name "Net-(PRO_RCodGB-Pad2)") (class "Default")
      (node (ref "PRO_RCodGB") (pin "2") (pinfunction "2_2") (pintype "passive"))
      (node (ref "PRO_codGauche") (pin "3") (pinfunction "3_3") (pintype "passive"))
    )
    (net (code "64") (name "Net-(PRO_STM32F4DISCOVERY-PE9{slash}FSMC_D6{slash}TIM1_CH1)") (class "Default")
      (node (ref "PRO_STM32F4DISCOVERY") (pin "27") (pinfunction "PE9/FSMC_D6/TIM1_CH1_27") (pintype "passive"))
      (node (ref "st_i_am_p") (pin "2") (pinfunction "2_2") (pintype "passive"))
    )
    (net (code "65") (name "unconnected-(PRO_STM32F4DISCOVERY-BOOT0{slash}VPP-Pad71)") (class "Default")
      (node (ref "PRO_STM32F4DISCOVERY") (pin "71") (pinfunction "BOOT0/VPP_71") (pintype "passive+no_connect"))
    )
    (net (code "66") (name "unconnected-(PRO_STM32F4DISCOVERY-NC-Pad48)") (class "Default")
      (node (ref "PRO_STM32F4DISCOVERY") (pin "48") (pinfunction "NC_48") (pintype "passive+no_connect"))
    )
    (net (code "67") (name "unconnected-(PRO_STM32F4DISCOVERY-NRST-Pad6)") (class "Default")
      (node (ref "PRO_STM32F4DISCOVERY") (pin "6") (pinfunction "NRST_6") (pintype "passive+no_connect"))
    )
    (net (code "68") (name "unconnected-(PRO_STM32F4DISCOVERY-PA0-WKUP{slash}USART2_CTS{slash}USART4_TX{slash}ETH_MII_CRS{slash}TIM2_CH1_ETR{slash}TIM5_CH1{slash}TIM8_ETR{slash}ADC123_IN0{slash}WKUP-Pad12)") (class "Default")
      (node (ref "PRO_STM32F4DISCOVERY") (pin "12") (pinfunction "PA0-WKUP/USART2_CTS/USART4_TX/ETH_MII_CRS/TIM2_CH1_ETR/TIM5_CH1/TIM8_ETR/ADC123_IN0/WKUP_12") (pintype "passive+no_connect"))
    )
    (net (code "69") (name "unconnected-(PRO_STM32F4DISCOVERY-PA4{slash}SPI1_NSS{slash}SPI3_NSS{slash}USART2_CK{slash}DCMI_HSYNC{slash}OTG_HS_SOF{slash}I2S3_WS{slash}ADC12_IN4{slash}DAC1_OUT-Pad16)") (class "Default")
      (node (ref "PRO_STM32F4DISCOVERY") (pin "16") (pinfunction "PA4/SPI1_NSS/SPI3_NSS/USART2_CK/DCMI_HSYNC/OTG_HS_SOF/I2S3_WS/ADC12_IN4/DAC1_OUT_16") (pintype "passive+no_connect"))
    )
    (net (code "70") (name "unconnected-(PRO_STM32F4DISCOVERY-PA5{slash}SPI1_SCK{slash}OTG_HS_ULPI_CK{slash}TIM2_CH1_ETR{slash}TIM8_CHIN{slash}ADC12_IN5{slash}DAC2_OUT-Pad15)") (class "Default")
      (node (ref "PRO_STM32F4DISCOVERY") (pin "15") (pinfunction "PA5/SPI1_SCK/OTG_HS_ULPI_CK/TIM2_CH1_ETR/TIM8_CHIN/ADC12_IN5/DAC2_OUT_15") (pintype "passive+no_connect"))
    )
    (net (code "71") (name "unconnected-(PRO_STM32F4DISCOVERY-PA6{slash}SPI1_MISO{slash}TIM8_BKIN{slash}TIM13_CH1{slash}DCMI_PIXCLK{slash}TIM3_CH1{slash}TIM1_BKIN{slash}ADC12_IN6-Pad18)") (class "Default")
      (node (ref "PRO_STM32F4DISCOVERY") (pin "18") (pinfunction "PA6/SPI1_MISO/TIM8_BKIN/TIM13_CH1/DCMI_PIXCLK/TIM3_CH1/TIM1_BKIN/ADC12_IN6_18") (pintype "passive+no_connect"))
    )
    (net (code "72") (name "unconnected-(PRO_STM32F4DISCOVERY-PA7{slash}SPI1_MOSI{slash}TIM8_CH1N{slash}TIM14_CH1TIM3_CH2{slash}ETH_MII_RX_DV{slash}TIM1_CH1N{slash}RMII_CRS_DV{slash}ADC12_IN7-Pad17)") (class "Default")
      (node (ref "PRO_STM32F4DISCOVERY") (pin "17") (pinfunction "PA7/SPI1_MOSI/TIM8_CH1N/TIM14_CH1TIM3_CH2/ETH_MII_RX_DV/TIM1_CH1N/RMII_CRS_DV/ADC12_IN7_17") (pintype "passive+no_connect"))
    )
    (net (code "73") (name "unconnected-(PRO_STM32F4DISCOVERY-PA8{slash}MCO1{slash}USART1_CK{slash}TIM1_CH1{slash}I2C3_SCL{slash}OTG_FS_SOF-Pad93)") (class "Default")
      (node (ref "PRO_STM32F4DISCOVERY") (pin "93") (pinfunction "PA8/MCO1/USART1_CK/TIM1_CH1/I2C3_SCL/OTG_FS_SOF_93") (pintype "passive+no_connect"))
    )
    (net (code "74") (name "unconnected-(PRO_STM32F4DISCOVERY-PA9{slash}USART1_TX{slash}TIM1_CH2{slash}I2C3_SMBA{slash}DCMI_D0{slash}OTG_FS_VBUS-Pad94)") (class "Default")
      (node (ref "PRO_STM32F4DISCOVERY") (pin "94") (pinfunction "PA9/USART1_TX/TIM1_CH2/I2C3_SMBA/DCMI_D0/OTG_FS_VBUS_94") (pintype "passive+no_connect"))
    )
    (net (code "75") (name "unconnected-(PRO_STM32F4DISCOVERY-PA10{slash}USART1_RX{slash}TIM1_CH3{slash}OTG_FS_ID{slash}DCMI_D1-Pad91)") (class "Default")
      (node (ref "PRO_STM32F4DISCOVERY") (pin "91") (pinfunction "PA10/USART1_RX/TIM1_CH3/OTG_FS_ID/DCMI_D1_91") (pintype "passive+no_connect"))
    )
    (net (code "76") (name "unconnected-(PRO_STM32F4DISCOVERY-PA13{slash}JTMS_SWDIO-Pad92)") (class "Default")
      (node (ref "PRO_STM32F4DISCOVERY") (pin "92") (pinfunction "PA13/JTMS_SWDIO_92") (pintype "passive+no_connect"))
    )
    (net (code "77") (name "unconnected-(PRO_STM32F4DISCOVERY-PA14{slash}JTCK_SWCLK-Pad89)") (class "Default")
      (node (ref "PRO_STM32F4DISCOVERY") (pin "89") (pinfunction "PA14/JTCK_SWCLK_89") (pintype "passive+no_connect"))
    )
    (net (code "78") (name "unconnected-(PRO_STM32F4DISCOVERY-PB2-Pad24)") (class "Default")
      (node (ref "PRO_STM32F4DISCOVERY") (pin "24") (pinfunction "PB2_24") (pintype "passive+no_connect"))
    )
    (net (code "79") (name "unconnected-(PRO_STM32F4DISCOVERY-PB3{slash}JTDO{slash}TRACESWO{slash}SPI3_SCK{slash}I2S3_CK{slash}TIM2_CH2{slash}SPI1_SCK-Pad78)") (class "Default")
      (node (ref "PRO_STM32F4DISCOVERY") (pin "78") (pinfunction "PB3/JTDO/TRACESWO/SPI3_SCK/I2S3_CK/TIM2_CH2/SPI1_SCK_78") (pintype "passive+no_connect"))
    )
    (net (code "80") (name "unconnected-(PRO_STM32F4DISCOVERY-PB9{slash}SPI2_NSS{slash}I2S2_WS{slash}TIM4_CH4{slash}TIM11_CH1{slash}OTG_FS_SDA{slash}SDIO_D5{slash}DCMI_D7{slash}I2C1_SDA{slash}CAN1_TX-Pad70)") (class "Default")
      (node (ref "PRO_STM32F4DISCOVERY") (pin "70") (pinfunction "PB9/SPI2_NSS/I2S2_WS/TIM4_CH4/TIM11_CH1/OTG_FS_SDA/SDIO_D5/DCMI_D7/I2C1_SDA/CAN1_TX_70") (pintype "passive+no_connect"))
    )
    (net (code "81") (name "unconnected-(PRO_STM32F4DISCOVERY-PB10{slash}SPI2_SCK{slash}I2S2_CK{slash}I2C2_SCL{slash}USART3_TX{slash}OTG_HS_ULPI_D3{slash}ETH_MII_RX_ER{slash}OTG_HS_SCL{slash}TIM2_CH3-Pad34)") (class "Default")
      (node (ref "PRO_STM32F4DISCOVERY") (pin "34") (pinfunction "PB10/SPI2_SCK/I2S2_CK/I2C2_SCL/USART3_TX/OTG_HS_ULPI_D3/ETH_MII_RX_ER/OTG_HS_SCL/TIM2_CH3_34") (pintype "passive+no_connect"))
    )
    (net (code "82") (name "unconnected-(PRO_STM32F4DISCOVERY-PB11{slash}I2C2_SDA{slash}USART3_RX{slash}OTG_HS_ULPI_D4{slash}ETH_RMII_TX_EN{slash}ETH_MII_TX_EN{slash}OTG_HS_SDA{slash}TIM2_CH4-Pad35)") (class "Default")
      (node (ref "PRO_STM32F4DISCOVERY") (pin "35") (pinfunction "PB11/I2C2_SDA/USART3_RX/OTG_HS_ULPI_D4/ETH_RMII_TX_EN/ETH_MII_TX_EN/OTG_HS_SDA/TIM2_CH4_35") (pintype "passive+no_connect"))
    )
    (net (code "83") (name "unconnected-(PRO_STM32F4DISCOVERY-PC0{slash}OTG_HS_ULPI_STP{slash}ADC123_IN10-Pad8)") (class "Default")
      (node (ref "PRO_STM32F4DISCOVERY") (pin "8") (pinfunction "PC0/OTG_HS_ULPI_STP/ADC123_IN10_8") (pintype "passive+no_connect"))
    )
    (net (code "84") (name "unconnected-(PRO_STM32F4DISCOVERY-PC5{slash}ETH_RMII_RX_D1{slash}ETH_MII_RX_D1{slash}ADC12_IN15-Pad19)") (class "Default")
      (node (ref "PRO_STM32F4DISCOVERY") (pin "19") (pinfunction "PC5/ETH_RMII_RX_D1/ETH_MII_RX_D1/ADC12_IN15_19") (pintype "passive+no_connect"))
    )
    (net (code "85") (name "unconnected-(PRO_STM32F4DISCOVERY-PC6{slash}I2S2_MCK{slash}TIM8_CH1{slash}SDIO_D6{slash}USART6_TX{slash}DCMI_D0{slash}TIM3_CH1-Pad97)") (class "Default")
      (node (ref "PRO_STM32F4DISCOVERY") (pin "97") (pinfunction "PC6/I2S2_MCK/TIM8_CH1/SDIO_D6/USART6_TX/DCMI_D0/TIM3_CH1_97") (pintype "passive+no_connect"))
    )
    (net (code "86") (name "unconnected-(PRO_STM32F4DISCOVERY-PC7{slash}I2S3_MCK{slash}TIM8_CH2{slash}SDIO_D7{slash}USART6_RX_DCMI_D1{slash}TIM3_CH2-Pad98)") (class "Default")
      (node (ref "PRO_STM32F4DISCOVERY") (pin "98") (pinfunction "PC7/I2S3_MCK/TIM8_CH2/SDIO_D7/USART6_RX_DCMI_D1/TIM3_CH2_98") (pintype "passive+no_connect"))
    )
    (net (code "87") (name "unconnected-(PRO_STM32F4DISCOVERY-PC10{slash}SPI3_SCK{slash}I2S3_CK{slash}UART4_TX{slash}SDIO_D2{slash}DCMI_D8{slash}USART3_TX-Pad87)") (class "Default")
      (node (ref "PRO_STM32F4DISCOVERY") (pin "87") (pinfunction "PC10/SPI3_SCK/I2S3_CK/UART4_TX/SDIO_D2/DCMI_D8/USART3_TX_87") (pintype "passive+no_connect"))
    )
    (net (code "88") (name "unconnected-(PRO_STM32F4DISCOVERY-PC14{slash}OSC32_IN-Pad59)") (class "Default")
      (node (ref "PRO_STM32F4DISCOVERY") (pin "59") (pinfunction "PC14/OSC32_IN_59") (pintype "passive+no_connect"))
    )
    (net (code "89") (name "unconnected-(PRO_STM32F4DISCOVERY-PC15{slash}OSC32_OUT-Pad60)") (class "Default")
      (node (ref "PRO_STM32F4DISCOVERY") (pin "60") (pinfunction "PC15/OSC32_OUT_60") (pintype "passive+no_connect"))
    )
    (net (code "90") (name "unconnected-(PRO_STM32F4DISCOVERY-PD2{slash}TIM3_ETR{slash}UART5_RXSDIO_CMD{slash}DCMI_D11-Pad84)") (class "Default")
      (node (ref "PRO_STM32F4DISCOVERY") (pin "84") (pinfunction "PD2/TIM3_ETR/UART5_RXSDIO_CMD/DCMI_D11_84") (pintype "passive+no_connect"))
    )
    (net (code "91") (name "unconnected-(PRO_STM32F4DISCOVERY-PD3{slash}FSMC_CLK{slash}USART2_CTS-Pad81)") (class "Default")
      (node (ref "PRO_STM32F4DISCOVERY") (pin "81") (pinfunction "PD3/FSMC_CLK/USART2_CTS_81") (pintype "passive+no_connect"))
    )
    (net (code "92") (name "unconnected-(PRO_STM32F4DISCOVERY-PD4{slash}FSMC_NOE{slash}USART2_RTS-Pad82)") (class "Default")
      (node (ref "PRO_STM32F4DISCOVERY") (pin "82") (pinfunction "PD4/FSMC_NOE/USART2_RTS_82") (pintype "passive+no_connect"))
    )
    (net (code "93") (name "unconnected-(PRO_STM32F4DISCOVERY-PD5{slash}FSMC_NWE{slash}USART2_TX-Pad79)") (class "Default")
      (node (ref "PRO_STM32F4DISCOVERY") (pin "79") (pinfunction "PD5/FSMC_NWE/USART2_TX_79") (pintype "passive+no_connect"))
    )
    (net (code "94") (name "unconnected-(PRO_STM32F4DISCOVERY-PD8{slash}FSMC_D13{slash}USART3_TX-Pad40)") (class "Default")
      (node (ref "PRO_STM32F4DISCOVERY") (pin "40") (pinfunction "PD8/FSMC_D13/USART3_TX_40") (pintype "passive+no_connect"))
    )
    (net (code "95") (name "unconnected-(PRO_STM32F4DISCOVERY-PD9{slash}FSMC_D14{slash}USART3_RX-Pad41)") (class "Default")
      (node (ref "PRO_STM32F4DISCOVERY") (pin "41") (pinfunction "PD9/FSMC_D14/USART3_RX_41") (pintype "passive+no_connect"))
    )
    (net (code "96") (name "unconnected-(PRO_STM32F4DISCOVERY-PE0{slash}TIM4_ETR{slash}FSMC_NBL0{slash}DCMI_D2-Pad67)") (class "Default")
      (node (ref "PRO_STM32F4DISCOVERY") (pin "67") (pinfunction "PE0/TIM4_ETR/FSMC_NBL0/DCMI_D2_67") (pintype "passive+no_connect"))
    )
    (net (code "97") (name "unconnected-(PRO_STM32F4DISCOVERY-PE1{slash}FSMC_NBL1{slash}DCMI_D3-Pad68)") (class "Default")
      (node (ref "PRO_STM32F4DISCOVERY") (pin "68") (pinfunction "PE1/FSMC_NBL1/DCMI_D3_68") (pintype "passive+no_connect"))
    )
    (net (code "98") (name "unconnected-(PRO_STM32F4DISCOVERY-PE2{slash}TRACECLK{slash}FSMC_A23{slash}ETH_MII_TXD3-Pad65)") (class "Default")
      (node (ref "PRO_STM32F4DISCOVERY") (pin "65") (pinfunction "PE2/TRACECLK/FSMC_A23/ETH_MII_TXD3_65") (pintype "passive+no_connect"))
    )
    (net (code "99") (name "unconnected-(PRO_STM32F4DISCOVERY-PE3{slash}TRACED0{slash}FSMC_A19-Pad66)") (class "Default")
      (node (ref "PRO_STM32F4DISCOVERY") (pin "66") (pinfunction "PE3/TRACED0/FSMC_A19_66") (pintype "passive+no_connect"))
    )
    (net (code "100") (name "unconnected-(PRO_STM32F4DISCOVERY-PE4{slash}TRACED1{slash}FSMC_A20{slash}DCMI_D4-Pad63)") (class "Default")
      (node (ref "PRO_STM32F4DISCOVERY") (pin "63") (pinfunction "PE4/TRACED1/FSMC_A20/DCMI_D4_63") (pintype "passive+no_connect"))
    )
    (net (code "101") (name "unconnected-(PRO_STM32F4DISCOVERY-PE5{slash}TRACED2{slash}FSMC_A21{slash}TIM9_CH1{slash}DCMI_D6-Pad64)") (class "Default")
      (node (ref "PRO_STM32F4DISCOVERY") (pin "64") (pinfunction "PE5/TRACED2/FSMC_A21/TIM9_CH1/DCMI_D6_64") (pintype "passive+no_connect"))
    )
    (net (code "102") (name "unconnected-(PRO_STM32F4DISCOVERY-PE6{slash}TRACED3{slash}FSMC_A22{slash}TIM9_CH2{slash}DCMI_D7-Pad61)") (class "Default")
      (node (ref "PRO_STM32F4DISCOVERY") (pin "61") (pinfunction "PE6/TRACED3/FSMC_A22/TIM9_CH2/DCMI_D7_61") (pintype "passive+no_connect"))
    )
    (net (code "103") (name "unconnected-(PRO_STM32F4DISCOVERY-PE7{slash}FSMC_D4{slash}TIM1_ETR-Pad25)") (class "Default")
      (node (ref "PRO_STM32F4DISCOVERY") (pin "25") (pinfunction "PE7/FSMC_D4/TIM1_ETR_25") (pintype "passive+no_connect"))
    )
    (net (code "104") (name "unconnected-(PRO_STM32F4DISCOVERY-PE8{slash}FSMC_D5{slash}TIM1_CH1N-Pad26)") (class "Default")
      (node (ref "PRO_STM32F4DISCOVERY") (pin "26") (pinfunction "PE8/FSMC_D5/TIM1_CH1N_26") (pintype "passive+no_connect"))
    )
    (net (code "105") (name "unconnected-(PRO_STM32F4DISCOVERY-PH0{slash}OSC_IN-Pad57)") (class "Default")
      (node (ref "PRO_STM32F4DISCOVERY") (pin "57") (pinfunction "PH0/OSC_IN_57") (pintype "passive+no_connect"))
    )
    (net (code "106") (name "unconnected-(PRO_STM32F4DISCOVERY-PH1{slash}OSC_OUT-Pad58)") (class "Default")
      (node (ref "PRO_STM32F4DISCOVERY") (pin "58") (pinfunction "PH1/OSC_OUT_58") (pintype "passive+no_connect"))
    )
    (net (code "107") (name "unconnected-(PRO_STM32F4DISCOVERY-VDD-Pad3)") (class "Default")
      (node (ref "PRO_STM32F4DISCOVERY") (pin "3") (pinfunction "VDD_3") (pintype "passive+no_connect"))
    )
    (net (code "108") (name "unconnected-(PRO_STM32F4DISCOVERY-VDD-Pad4)") (class "Default")
      (node (ref "PRO_STM32F4DISCOVERY") (pin "4") (pinfunction "VDD_4") (pintype "passive+no_connect"))
    )
    (net (code "109") (name "unconnected-(PRO_STM32F4DISCOVERY-VDD-Pad72)") (class "Default")
      (node (ref "PRO_STM32F4DISCOVERY") (pin "72") (pinfunction "VDD_72") (pintype "passive+no_connect"))
    )
    (net (code "110") (name "unconnected-(PRO_Ucan-VREF-Pad5)") (class "Default")
      (node (ref "PRO_Ucan") (pin "5") (pinfunction "VREF_5") (pintype "output+no_connect"))
    )
  )
)
